# Subtractor.net
KiCad netlist of a schematic drawn in Altium Designer
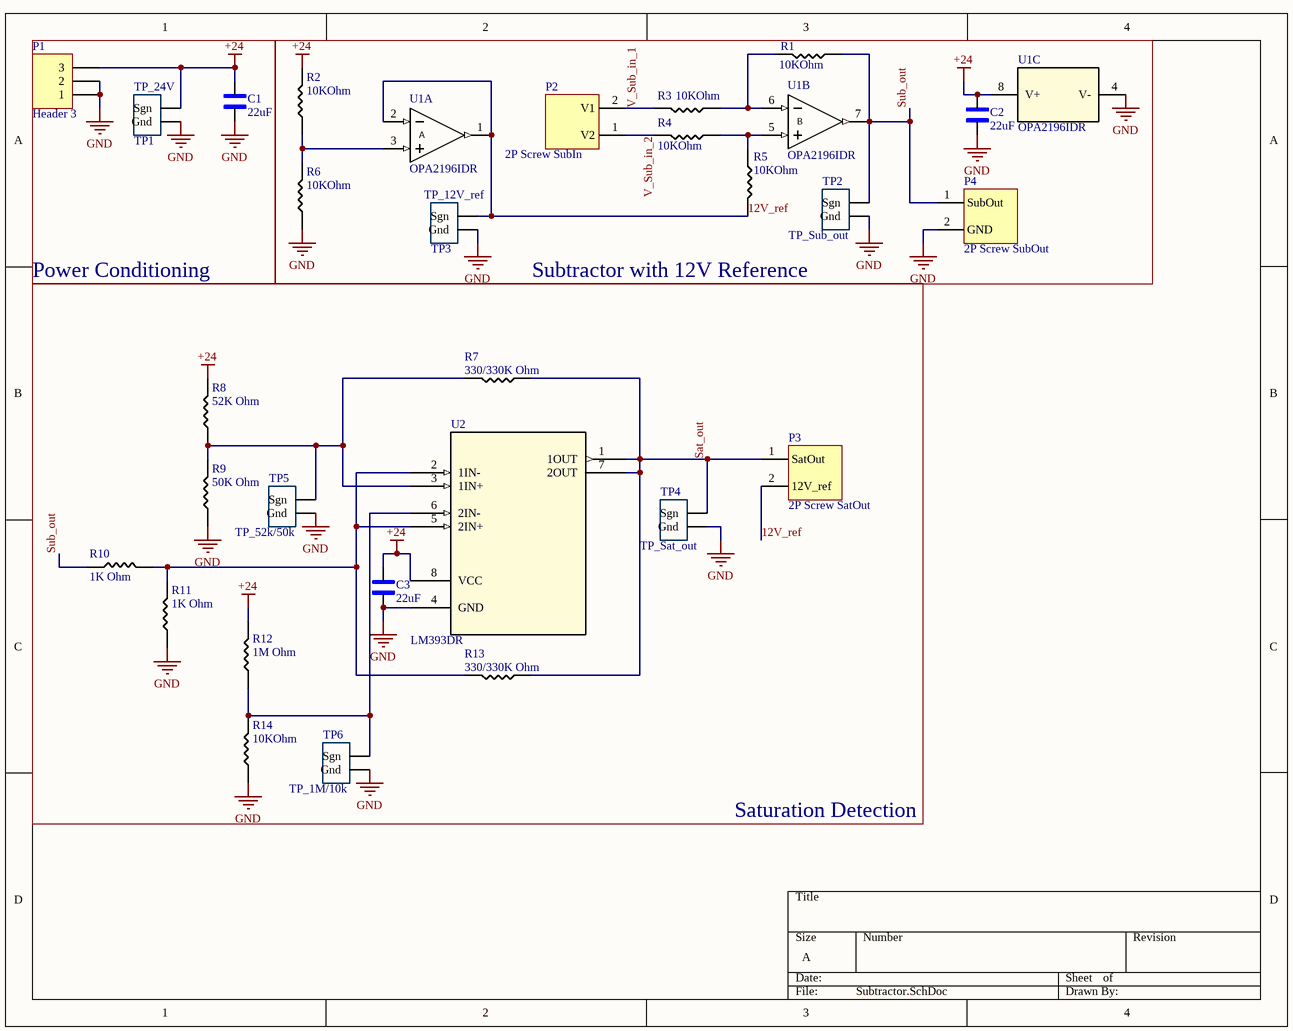
[diagram p0: Subtractor.SchDoc]

(export (version "E")
  (design (tool "Eeschema 10.0.6"))
  (components
    (comp (ref "C1")
      (value "22uF")
      (footprint "1206_Passive_Capacitor")
      (description "22uF ±10% 25V X5R 1206 Multilayer Ceramic Capacitors MLCC - SMD/SMT RoHS")
      (fields (field (name "MFR PART #") "CL31A226KAHNNNE") (field (name "LCSC PART#") "C12891"))
      (libsource (lib "ECEN5730Lib_2023_05_DS") (part "C_22uF_1206"))
    )
    (comp (ref "C2")
      (value "22uF")
      (footprint "1206_Passive_Capacitor")
      (description "22uF ±10% 25V X5R 1206 Multilayer Ceramic Capacitors MLCC - SMD/SMT RoHS")
      (fields (field (name "MFR PART #") "CL31A226KAHNNNE") (field (name "LCSC PART#") "C12891"))
      (libsource (lib "ECEN5730Lib_2023_05_DS") (part "C_22uF_1206"))
    )
    (comp (ref "C3")
      (value "22uF")
      (footprint "1206_Passive_Capacitor")
      (description "22uF ±10% 25V X5R 1206 Multilayer Ceramic Capacitors MLCC - SMD/SMT RoHS")
      (fields (field (name "MFR PART #") "CL31A226KAHNNNE") (field (name "LCSC PART#") "C12891"))
      (libsource (lib "ECEN5730Lib_2023_05_DS") (part "C_22uF_1206"))
    )
    (comp (ref "P1")
      (value "Header 3")
      (footprint "HDR1X3")
      (description "Header, 3-Pin")
      (fields (field (name "PUBLISHER") "Altium Limited"))
      (libsource (lib "Miscellaneous Connectors") (part "Header 3"))
    )
    (comp (ref "P2")
      (value "2P Screw SubIn")
      (footprint "P_Terminal block 3.5mm-pitch")
      (description "Green Straight pin 3.5mm  pitch; P=3.5mm  Screw terminal ROHS")
      (fields (field (name "MFR PART #") "KF350-3.5-2P") (field (name "MANUFACTURER") "Cixi Kefa Elec"))
      (libsource (lib "") (part "P_Terminal block_1"))
    )
    (comp (ref "P3")
      (value "2P Screw SatOut")
      (footprint "P_Terminal block 3.5mm-pitch")
      (description "Green Straight pin 3.5mm  pitch; P=3.5mm  Screw terminal ROHS")
      (fields (field (name "MFR PART #") "KF350-3.5-2P") (field (name "MANUFACTURER") "Cixi Kefa Elec"))
      (libsource (lib "ECEN5730Lib_2023_05_DS") (part "P_Terminal block"))
    )
    (comp (ref "P4")
      (value "2P Screw SubOut")
      (footprint "P_Terminal block 3.5mm-pitch")
      (description "Green Straight pin 3.5mm  pitch; P=3.5mm  Screw terminal ROHS")
      (fields (field (name "MFR PART #") "KF350-3.5-2P") (field (name "MANUFACTURER") "Cixi Kefa Elec"))
      (libsource (lib "ECEN5730Lib_2023_05_DS") (part "P_Terminal block"))
    )
    (comp (ref "R1")
      (value "10KOhm")
      (footprint "1206_Passive_Resitor")
      (description "10 kOhms ±5% 0.25W, 1/4W Chip Resistor 1206 (3216 Metric) Automotive AEC-Q200 Thick Film")
      (fields (field (name "MFR PART #") "RMCF1206FT10K0") (field (name "LCSC PART#") "C17902"))
      (libsource (lib "ECEN5730Lib_2023_05_DS") (part "R_10KOhm_1206"))
    )
    (comp (ref "R2")
      (value "10KOhm")
      (footprint "1206_Passive_Resitor")
      (description "10 kOhms ±5% 0.25W, 1/4W Chip Resistor 1206 (3216 Metric) Automotive AEC-Q200 Thick Film")
      (fields (field (name "MFR PART #") "RMCF1206FT10K0") (field (name "LCSC PART#") "C17902"))
      (libsource (lib "ECEN5730Lib_2023_05_DS") (part "R_10KOhm_1206"))
    )
    (comp (ref "R3")
      (value "10KOhm")
      (footprint "1206_Passive_Resitor")
      (description "10 kOhms ±5% 0.25W, 1/4W Chip Resistor 1206 (3216 Metric) Automotive AEC-Q200 Thick Film")
      (fields (field (name "MFR PART #") "RMCF1206FT10K0") (field (name "LCSC PART#") "C17902"))
      (libsource (lib "ECEN5730Lib_2023_05_DS") (part "R_10KOhm_1206"))
    )
    (comp (ref "R4")
      (value "10KOhm")
      (footprint "1206_Passive_Resitor")
      (description "10 kOhms ±5% 0.25W, 1/4W Chip Resistor 1206 (3216 Metric) Automotive AEC-Q200 Thick Film")
      (fields (field (name "MFR PART #") "RMCF1206FT10K0") (field (name "LCSC PART#") "C17902"))
      (libsource (lib "ECEN5730Lib_2023_05_DS") (part "R_10KOhm_1206"))
    )
    (comp (ref "R5")
      (value "10KOhm")
      (footprint "1206_Passive_Resitor")
      (description "10 kOhms ±5% 0.25W, 1/4W Chip Resistor 1206 (3216 Metric) Automotive AEC-Q200 Thick Film")
      (fields (field (name "MFR PART #") "RMCF1206FT10K0") (field (name "LCSC PART#") "C17902"))
      (libsource (lib "ECEN5730Lib_2023_05_DS") (part "R_10KOhm_1206"))
    )
    (comp (ref "R6")
      (value "10KOhm")
      (footprint "1206_Passive_Resitor")
      (description "10 kOhms ±5% 0.25W, 1/4W Chip Resistor 1206 (3216 Metric) Automotive AEC-Q200 Thick Film")
      (fields (field (name "MFR PART #") "RMCF1206FT10K0") (field (name "LCSC PART#") "C17902"))
      (libsource (lib "ECEN5730Lib_2023_05_DS") (part "R_10KOhm_1206"))
    )
    (comp (ref "R7")
      (value "330/330K Ohm")
      (footprint "1206_Passive_Resitor")
      (description "CHIP RESISTOR - SURFACE MOUNT 1KOHMS ±1% 1/4W 1206 ROHS")
      (fields (field (name "MFR PART #") "RNCP1206FTD1K00CT") (field (name "LCSC PART#") "C4410"))
      (libsource (lib "ECEN5730Lib_2023_05_DS") (part "R_1K_1206"))
    )
    (comp (ref "R8")
      (value "52K Ohm")
      (footprint "1206_Passive_Resitor")
      (description "CHIP RESISTOR - SURFACE MOUNT 1KOHMS ±1% 1/4W 1206 ROHS")
      (fields (field (name "MFR PART #") "RNCP1206FTD1K00CT") (field (name "LCSC PART#") "C4410"))
      (libsource (lib "ECEN5730Lib_2023_05_DS") (part "R_1K_1206"))
    )
    (comp (ref "R9")
      (value "50K Ohm")
      (footprint "1206_Passive_Resitor")
      (description "CHIP RESISTOR - SURFACE MOUNT 1KOHMS ±1% 1/4W 1206 ROHS")
      (fields (field (name "MFR PART #") "RNCP1206FTD1K00CT") (field (name "LCSC PART#") "C4410"))
      (libsource (lib "ECEN5730Lib_2023_05_DS") (part "R_1K_1206"))
    )
    (comp (ref "R10")
      (value "1K Ohm")
      (footprint "1206_Passive_Resitor")
      (description "CHIP RESISTOR - SURFACE MOUNT 1KOHMS ±1% 1/4W 1206 ROHS")
      (fields (field (name "MFR PART #") "RNCP1206FTD1K00CT") (field (name "LCSC PART#") "C4410"))
      (libsource (lib "ECEN5730Lib_2023_05_DS") (part "R_1K_1206"))
    )
    (comp (ref "R11")
      (value "1K Ohm")
      (footprint "1206_Passive_Resitor")
      (description "CHIP RESISTOR - SURFACE MOUNT 1KOHMS ±1% 1/4W 1206 ROHS")
      (fields (field (name "MFR PART #") "RNCP1206FTD1K00CT") (field (name "LCSC PART#") "C4410"))
      (libsource (lib "ECEN5730Lib_2023_05_DS") (part "R_1K_1206"))
    )
    (comp (ref "R12")
      (value "1M Ohm")
      (footprint "1206_Passive_Resitor")
      (description "CHIP RESISTOR - SURFACE MOUNT 1MOHMS ±1% 1/4W 1206 ROHS")
      (fields (field (name "MFR PART #") "RMCF1206JT1M00") (field (name "LCSC PART#") "C17927"))
      (libsource (lib "ECEN5730Lib_2023_05_DS") (part "R_1M_1206"))
    )
    (comp (ref "R13")
      (value "330/330K Ohm")
      (footprint "1206_Passive_Resitor")
      (description "CHIP RESISTOR - SURFACE MOUNT 1KOHMS ±1% 1/4W 1206 ROHS")
      (fields (field (name "MFR PART #") "RNCP1206FTD1K00CT") (field (name "LCSC PART#") "C4410"))
      (libsource (lib "ECEN5730Lib_2023_05_DS") (part "R_1K_1206"))
    )
    (comp (ref "R14")
      (value "10KOhm")
      (footprint "1206_Passive_Resitor")
      (description "10 kOhms ±5% 0.25W, 1/4W Chip Resistor 1206 (3216 Metric) Automotive AEC-Q200 Thick Film")
      (fields (field (name "MFR PART #") "RMCF1206FT10K0") (field (name "LCSC PART#") "C17902"))
      (libsource (lib "ECEN5730Lib_2023_05_DS") (part "R_10KOhm_1206"))
    )
    (comp (ref "TP1")
      (value "TP_24V")
      (footprint "TP10x_Probe")
      (description "Test Point 300 mil centers")
      (libsource (lib "ECEN5730Lib_2023_05_DS") (part "TP_10x_Probe"))
    )
    (comp (ref "TP2")
      (value "TP_Sub_out")
      (footprint "TP10x_Probe")
      (description "Test Point 300 mil centers")
      (libsource (lib "ECEN5730Lib_2023_05_DS") (part "TP_10x_Probe"))
    )
    (comp (ref "TP3")
      (value "TP_12V_ref")
      (footprint "TP10x_Probe")
      (description "Test Point 300 mil centers")
      (libsource (lib "ECEN5730Lib_2023_05_DS") (part "TP_10x_Probe"))
    )
    (comp (ref "TP4")
      (value "TP_Sat_out")
      (footprint "TP10x_Probe")
      (description "Test Point 300 mil centers")
      (libsource (lib "ECEN5730Lib_2023_05_DS") (part "TP_10x_Probe"))
    )
    (comp (ref "TP5")
      (value "TP_52k/50k")
      (footprint "TP10x_Probe")
      (description "Test Point 300 mil centers")
      (libsource (lib "ECEN5730Lib_2023_05_DS") (part "TP_10x_Probe"))
    )
    (comp (ref "TP6")
      (value "TP_1M/10k")
      (footprint "TP10x_Probe")
      (description "Test Point 300 mil centers")
      (libsource (lib "ECEN5730Lib_2023_05_DS") (part "TP_10x_Probe"))
    )
    (comp (ref "U1")
      (value "OPA2196IDR")
      (footprint "D0008A_N")
      (description "Dual, 36-V, low power, all-purpose amplifier with mux-friendly input 8-SOIC -40 to 125")
      (fields (field (name "COPYRIGHT") "Copyright (C) 2026 Ultra Librarian. All rights reserved."))
      (libsource (lib "Integrated_Library1") (part "OPA2196IDR"))
    )
    (comp (ref "U2")
      (value "LM393DR")
      (footprint "D8")
      (description "Dual differential comparator, commercial grade 8-SOIC 0 to 70")
      (fields (field (name "COPYRIGHT") "Copyright (C) 2025 Ultra Librarian. All rights reserved."))
      (libsource (lib "LM393DR") (part "LM393DR"))
    )
  )
  (nets
    (net (code "1") (name "+24") (class "Default")
      (node (ref "C1") (pin "2") (pinfunction "2_2") (pintype "passive"))
      (node (ref "C2") (pin "2") (pinfunction "2_2") (pintype "passive"))
      (node (ref "C3") (pin "2") (pinfunction "2_2") (pintype "passive"))
      (node (ref "P1") (pin "3") (pinfunction "3_3") (pintype "passive"))
      (node (ref "R12") (pin "2") (pinfunction "2_2") (pintype "passive"))
      (node (ref "R2") (pin "2") (pinfunction "2_2") (pintype "passive"))
      (node (ref "R8") (pin "2") (pinfunction "2_2") (pintype "passive"))
      (node (ref "TP1") (pin "1") (pinfunction "Sgn_1") (pintype "passive"))
      (node (ref "U1") (pin "8") (pinfunction "V+_8") (pintype "power_in"))
      (node (ref "U2") (pin "8") (pinfunction "VCC_8") (pintype "power_in"))
    )
    (net (code "2") (name "/12V_ref") (class "Default")
      (node (ref "P3") (pin "2") (pinfunction "12V_ref_2") (pintype "passive"))
      (node (ref "R5") (pin "2") (pinfunction "2_2") (pintype "passive"))
      (node (ref "TP3") (pin "1") (pinfunction "Sgn_1") (pintype "passive"))
      (node (ref "U1") (pin "1") (pinfunction "OUT_1") (pintype "output"))
      (node (ref "U1") (pin "2") (pinfunction "IN-_2") (pintype "input"))
    )
    (net (code "3") (name "/Sat_out") (class "Default")
      (node (ref "P3") (pin "1") (pinfunction "SatOut_1") (pintype "passive"))
      (node (ref "R13") (pin "1") (pinfunction "1_1") (pintype "passive"))
      (node (ref "R7") (pin "1") (pinfunction "1_1") (pintype "passive"))
      (node (ref "TP4") (pin "1") (pinfunction "Sgn_1") (pintype "passive"))
      (node (ref "U2") (pin "1") (pinfunction "1OUT_1") (pintype "output"))
      (node (ref "U2") (pin "7") (pinfunction "2OUT_7") (pintype "passive"))
    )
    (net (code "4") (name "/Sub_out") (class "Default")
      (node (ref "P4") (pin "1") (pinfunction "SatOut_1") (pintype "passive"))
      (node (ref "R1") (pin "1") (pinfunction "1_1") (pintype "passive"))
      (node (ref "R10") (pin "1") (pinfunction "1_1") (pintype "passive"))
      (node (ref "TP2") (pin "1") (pinfunction "Sgn_1") (pintype "passive"))
      (node (ref "U1") (pin "7") (pinfunction "OUT_7") (pintype "output"))
    )
    (net (code "5") (name "/V_Sub_in_1") (class "Default")
      (node (ref "P2") (pin "2") (pinfunction "V1_2") (pintype "passive"))
      (node (ref "R3") (pin "2") (pinfunction "2_2") (pintype "passive"))
    )
    (net (code "6") (name "/V_Sub_in_2") (class "Default")
      (node (ref "P2") (pin "1") (pinfunction "V2_1") (pintype "passive"))
      (node (ref "R4") (pin "2") (pinfunction "2_2") (pintype "passive"))
    )
    (net (code "7") (name "GND") (class "Default")
      (node (ref "C1") (pin "1") (pinfunction "1_1") (pintype "passive"))
      (node (ref "C2") (pin "1") (pinfunction "1_1") (pintype "passive"))
      (node (ref "C3") (pin "1") (pinfunction "1_1") (pintype "passive"))
      (node (ref "P1") (pin "1") (pinfunction "1_1") (pintype "passive"))
      (node (ref "P1") (pin "2") (pinfunction "2_2") (pintype "passive"))
      (node (ref "P4") (pin "2") (pinfunction "12V_ref_2") (pintype "passive"))
      (node (ref "R11") (pin "1") (pinfunction "1_1") (pintype "passive"))
      (node (ref "R14") (pin "1") (pinfunction "1_1") (pintype "passive"))
      (node (ref "R6") (pin "1") (pinfunction "1_1") (pintype "passive"))
      (node (ref "R9") (pin "1") (pinfunction "1_1") (pintype "passive"))
      (node (ref "TP1") (pin "2") (pinfunction "Gnd_2") (pintype "passive"))
      (node (ref "TP2") (pin "2") (pinfunction "Gnd_2") (pintype "passive"))
      (node (ref "TP3") (pin "2") (pinfunction "Gnd_2") (pintype "passive"))
      (node (ref "TP4") (pin "2") (pinfunction "Gnd_2") (pintype "passive"))
      (node (ref "TP5") (pin "2") (pinfunction "Gnd_2") (pintype "passive"))
      (node (ref "TP6") (pin "2") (pinfunction "Gnd_2") (pintype "passive"))
      (node (ref "U1") (pin "4") (pinfunction "V-_4") (pintype "power_in"))
      (node (ref "U2") (pin "4") (pinfunction "GND_4") (pintype "power_in"))
    )
    (net (code "8") (name "Net-(TP5-Sgn)") (class "Default")
      (node (ref "R7") (pin "2") (pinfunction "2_2") (pintype "passive"))
      (node (ref "R8") (pin "1") (pinfunction "1_1") (pintype "passive"))
      (node (ref "R9") (pin "2") (pinfunction "2_2") (pintype "passive"))
      (node (ref "TP5") (pin "1") (pinfunction "Sgn_1") (pintype "passive"))
      (node (ref "U2") (pin "3") (pinfunction "1IN+_3") (pintype "input"))
    )
    (net (code "9") (name "Net-(TP6-Sgn)") (class "Default")
      (node (ref "R12") (pin "1") (pinfunction "1_1") (pintype "passive"))
      (node (ref "R14") (pin "2") (pinfunction "2_2") (pintype "passive"))
      (node (ref "TP6") (pin "1") (pinfunction "Sgn_1") (pintype "passive"))
      (node (ref "U2") (pin "6") (pinfunction "2IN-_6") (pintype "input"))
    )
    (net (code "10") (name "Net-(U1A-IN+)") (class "Default")
      (node (ref "R2") (pin "1") (pinfunction "1_1") (pintype "passive"))
      (node (ref "R6") (pin "2") (pinfunction "2_2") (pintype "passive"))
      (node (ref "U1") (pin "3") (pinfunction "IN+_3") (pintype "input"))
    )
    (net (code "11") (name "Net-(U1B-IN+)") (class "Default")
      (node (ref "R4") (pin "1") (pinfunction "1_1") (pintype "passive"))
      (node (ref "R5") (pin "1") (pinfunction "1_1") (pintype "passive"))
      (node (ref "U1") (pin "5") (pinfunction "IN+_5") (pintype "input"))
    )
    (net (code "12") (name "Net-(U1B-IN-)") (class "Default")
      (node (ref "R1") (pin "2") (pinfunction "2_2") (pintype "passive"))
      (node (ref "R3") (pin "1") (pinfunction "1_1") (pintype "passive"))
      (node (ref "U1") (pin "6") (pinfunction "IN-_6") (pintype "input"))
    )
    (net (code "13") (name "Net-(U2-1IN-)") (class "Default")
      (node (ref "R10") (pin "2") (pinfunction "2_2") (pintype "passive"))
      (node (ref "R11") (pin "2") (pinfunction "2_2") (pintype "passive"))
      (node (ref "R13") (pin "2") (pinfunction "2_2") (pintype "passive"))
      (node (ref "U2") (pin "2") (pinfunction "1IN-_2") (pintype "input"))
      (node (ref "U2") (pin "5") (pinfunction "2IN+_5") (pintype "input"))
    )
  )
)
